# design.net
KiCad netlist of a schematic drawn in EasyEDA
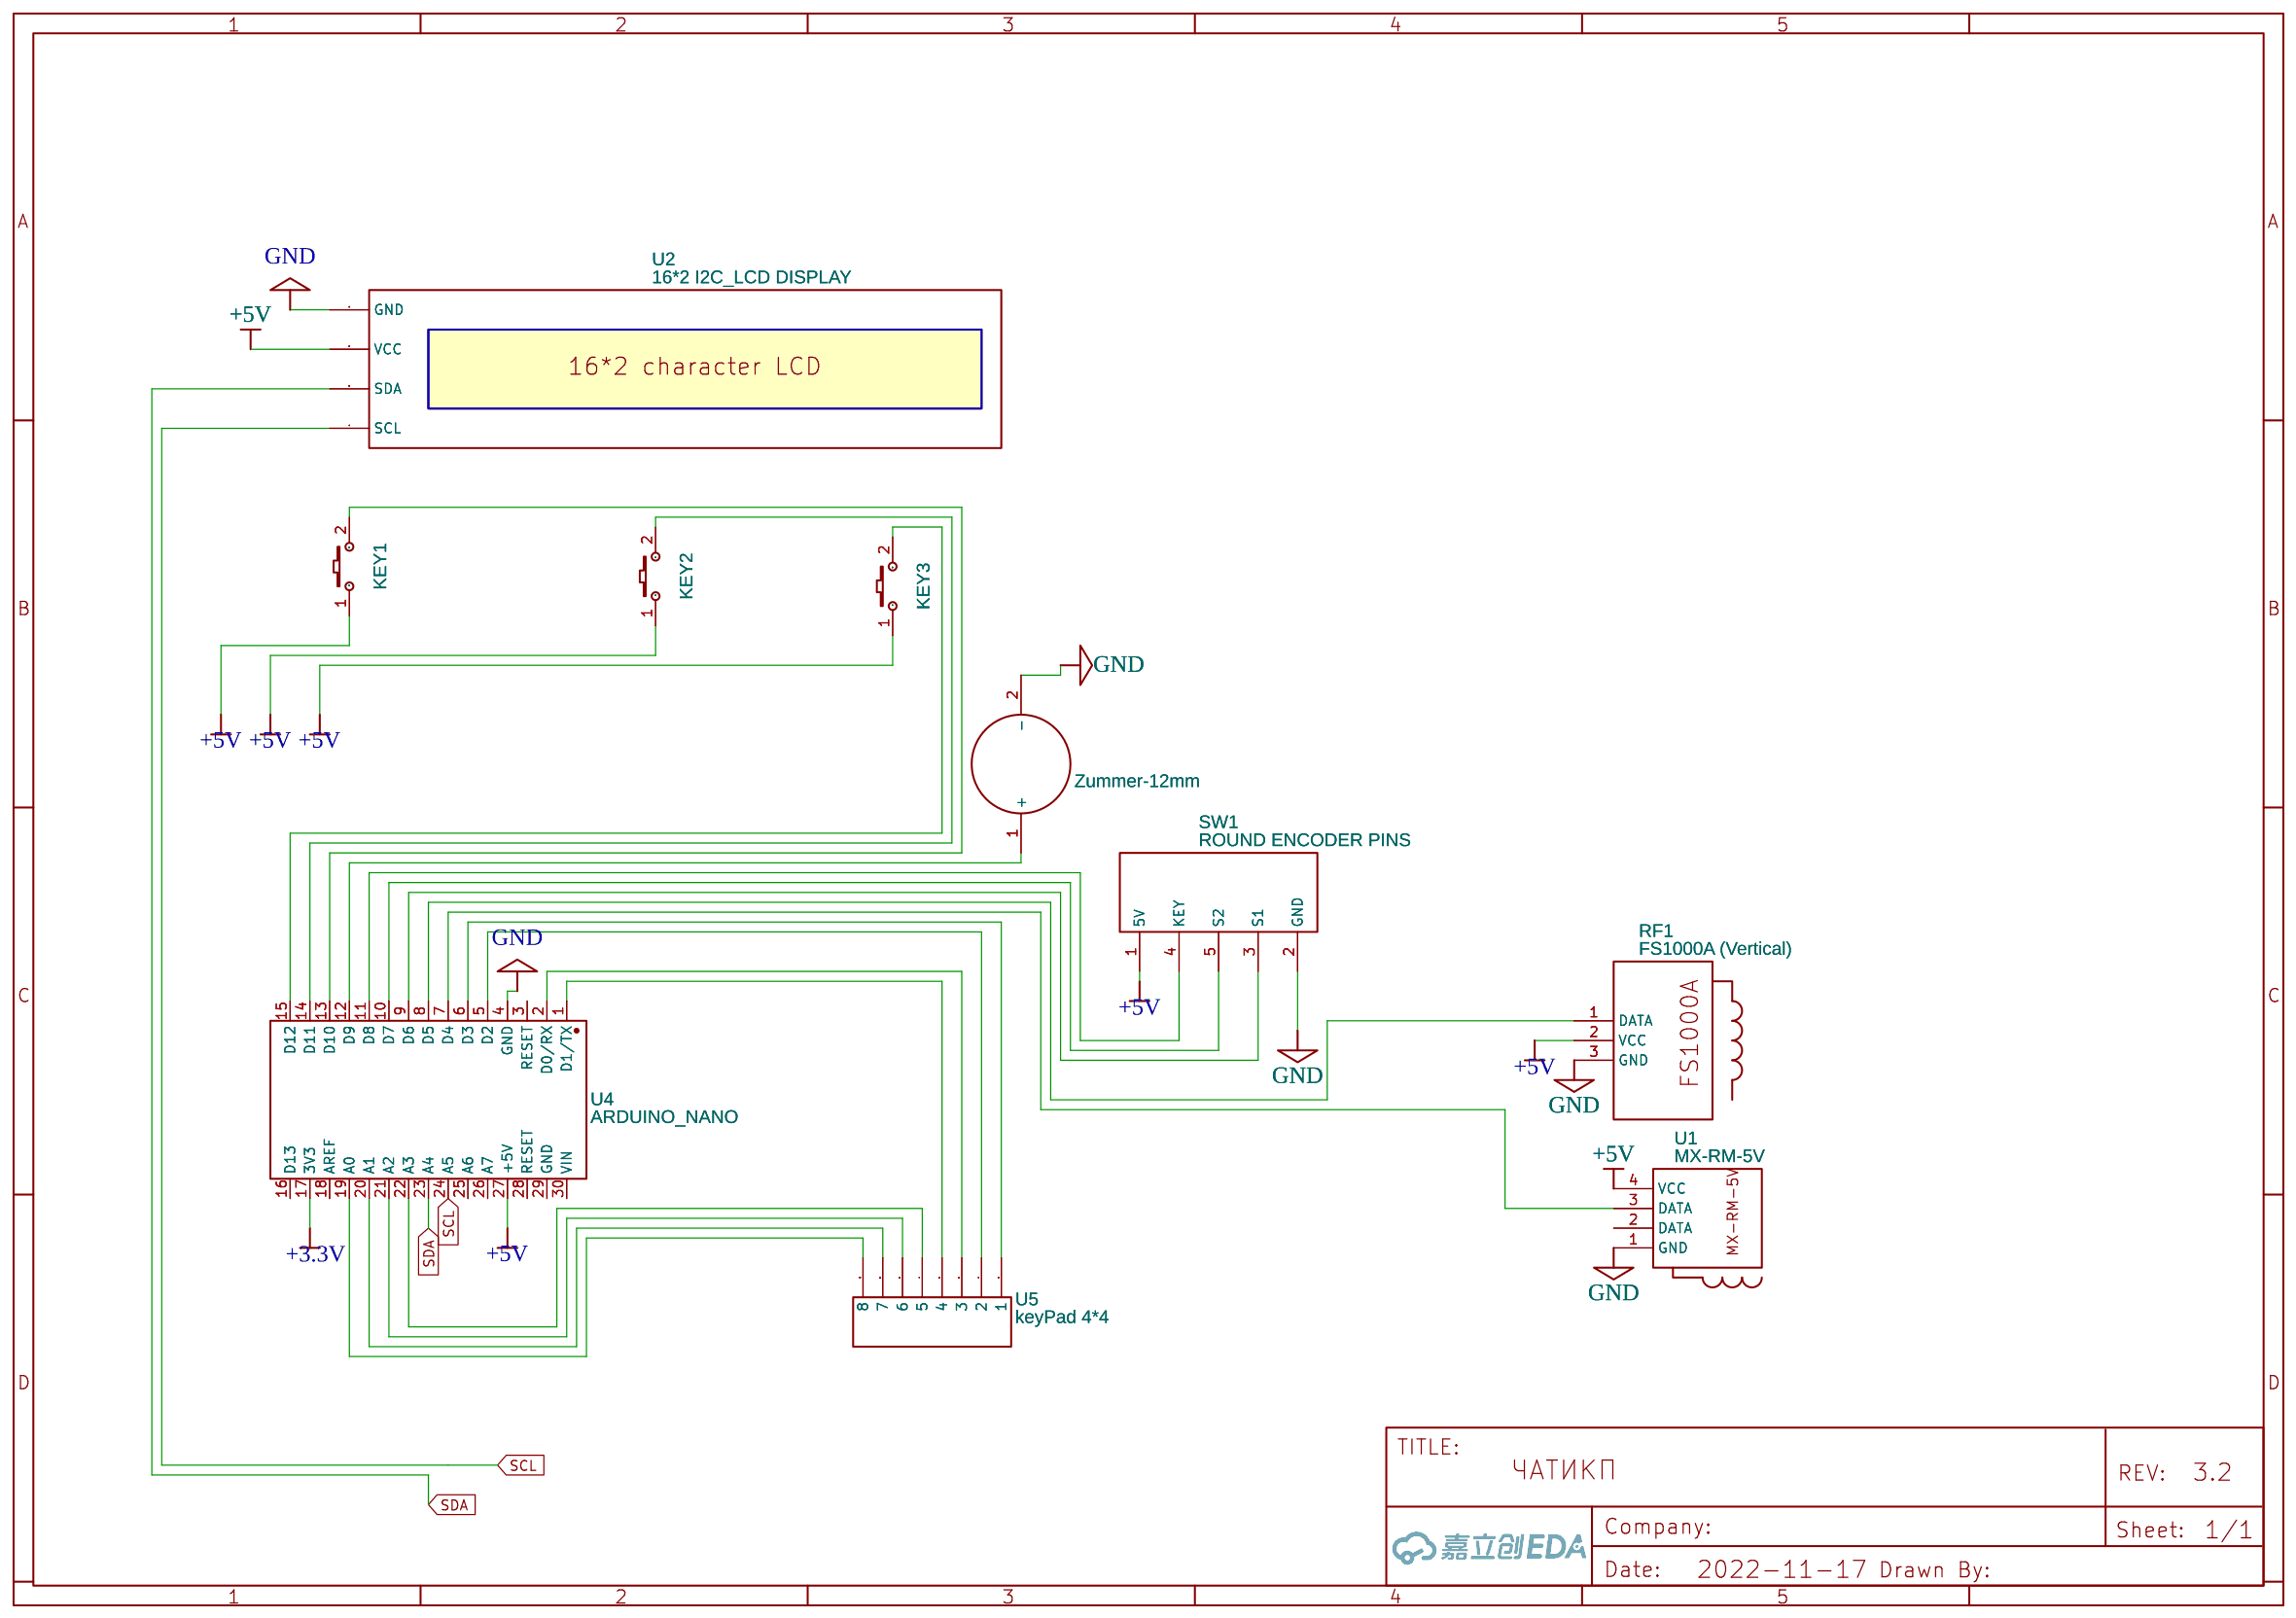
[diagram p0: schematic sheet]

(export (version "E")
  (design (tool "Eeschema 10.0.6"))
  (components
    (comp (ref "KEY1")
      (value "K2-3.6×6.1_SMD")
      (fields
        (field (name "BOM_Manufacturer Part") "K2-1107ST-A4SW-06")
        (field (name "BOM_Supplier Part") "C118141")
      )
      (libsource (lib "") (part "K2-3.6×6.1_SMD"))
    )
    (comp (ref "KEY2")
      (value "K2-3.6×6.1_SMD")
      (fields
        (field (name "BOM_Manufacturer Part") "K2-1107ST-A4SW-06")
        (field (name "BOM_Supplier Part") "C118141")
      )
      (libsource (lib "") (part "K2-3.6×6.1_SMD"))
    )
    (comp (ref "KEY3")
      (value "K2-3.6×6.1_SMD")
      (fields
        (field (name "BOM_Manufacturer Part") "K2-1107ST-A4SW-06")
        (field (name "BOM_Supplier Part") "C118141")
      )
      (libsource (lib "") (part "K2-3.6×6.1_SMD"))
    )
    (comp (ref "RF1") (value "FS1000A (Vertical)") (libsource (lib "") (part "FS1000A (Vertical)")))
    (comp (ref "SW1")
      (value "ROUND ENCODER PINS")
      (fields
        (field (name "BOM_Manufacturer Part") "PEC11R-4015F-S0024")
        (field (name "BOM_Supplier Part") "C143789")
      )
      (libsource (lib "") (part "ROUND ENCODER PINS"))
    )
    (comp (ref "U1") (value "MX-RM-5V") (libsource (lib "") (part "MX-RM-5V")))
    (comp (ref "U2")
      (value "16*2 I2C_LCD DISPLAY")
      (fields (field (name "BOM_Supplier Part") "undefined"))
      (libsource (lib "") (part "16*2 I2C_LCD DISPLAY"))
    )
    (comp (ref "U3") (value "Zummer-12mm") (libsource (lib "") (part "Y_Zummer-12mm")))
    (comp (ref "U4")
      (value "ARDUINO_NANO")
      (fields (field (name "BOM_Supplier Part") "C9900017879"))
      (libsource (lib "") (part "ARDUINO_NANO"))
    )
    (comp (ref "U5") (value "keyPad 4*4") (libsource (lib "") (part "keyPad 4*4")))
  )
  (nets
    (net (code "1") (name "+3.3V") (class "Default")
      (node (ref "U4") (pin "17") (pinfunction "3V3_17") (pintype "unspecified"))
    )
    (net (code "2") (name "+5V") (class "Default")
      (node (ref "KEY1") (pin "1") (pinfunction "1_1") (pintype "unspecified"))
      (node (ref "KEY2") (pin "1") (pinfunction "1_1") (pintype "unspecified"))
      (node (ref "KEY3") (pin "1") (pinfunction "1_1") (pintype "unspecified"))
      (node (ref "RF1") (pin "2") (pinfunction "VCC_2") (pintype "unspecified"))
      (node (ref "SW1") (pin "1") (pinfunction "5V_1") (pintype "unspecified"))
      (node (ref "U1") (pin "4") (pinfunction "VCC_4") (pintype "unspecified"))
      (node (ref "U2") (pin "2") (pinfunction "VCC_2") (pintype "unspecified"))
      (node (ref "U4") (pin "27") (pinfunction "+5V_27") (pintype "unspecified"))
    )
    (net (code "3") (name "GND") (class "Default")
      (node (ref "RF1") (pin "3") (pinfunction "GND_3") (pintype "unspecified"))
      (node (ref "SW1") (pin "2") (pinfunction "GND_2") (pintype "unspecified"))
      (node (ref "U1") (pin "1") (pinfunction "GND_1") (pintype "unspecified"))
      (node (ref "U2") (pin "1") (pinfunction "GND_1") (pintype "unspecified"))
      (node (ref "U3") (pin "2") (pinfunction "-_2") (pintype "unspecified"))
      (node (ref "U4") (pin "4") (pinfunction "GND_4") (pintype "unspecified"))
    )
    (net (code "4") (name "Net-(RF1-DATA)") (class "Default")
      (node (ref "RF1") (pin "1") (pinfunction "DATA_1") (pintype "unspecified"))
      (node (ref "U4") (pin "8") (pinfunction "D5_8") (pintype "unspecified"))
    )
    (net (code "5") (name "Net-(SW1-KEY)") (class "Default")
      (node (ref "SW1") (pin "4") (pinfunction "KEY_4") (pintype "unspecified"))
      (node (ref "U4") (pin "11") (pinfunction "D8_11") (pintype "unspecified"))
    )
    (net (code "6") (name "Net-(SW1-S1)") (class "Default")
      (node (ref "SW1") (pin "3") (pinfunction "S1_3") (pintype "unspecified"))
      (node (ref "U4") (pin "9") (pinfunction "D6_9") (pintype "unspecified"))
    )
    (net (code "7") (name "Net-(SW1-S2)") (class "Default")
      (node (ref "SW1") (pin "5") (pinfunction "S2_5") (pintype "unspecified"))
      (node (ref "U4") (pin "10") (pinfunction "D7_10") (pintype "unspecified"))
    )
    (net (code "8") (name "Net-(U3-+)") (class "Default")
      (node (ref "U3") (pin "1") (pinfunction "+_1") (pintype "unspecified"))
      (node (ref "U4") (pin "12") (pinfunction "D9_12") (pintype "unspecified"))
    )
    (net (code "9") (name "Net-(U4-A0)") (class "Default")
      (node (ref "U4") (pin "19") (pinfunction "A0_19") (pintype "unspecified"))
      (node (ref "U5") (pin "10") (pinfunction "8_10") (pintype "unspecified"))
    )
    (net (code "10") (name "Net-(U4-A1)") (class "Default")
      (node (ref "U4") (pin "20") (pinfunction "A1_20") (pintype "unspecified"))
      (node (ref "U5") (pin "9") (pinfunction "7_9") (pintype "unspecified"))
    )
    (net (code "11") (name "Net-(U4-A2)") (class "Default")
      (node (ref "U4") (pin "21") (pinfunction "A2_21") (pintype "unspecified"))
      (node (ref "U5") (pin "8") (pinfunction "6_8") (pintype "unspecified"))
    )
    (net (code "12") (name "Net-(U4-A3)") (class "Default")
      (node (ref "U4") (pin "22") (pinfunction "A3_22") (pintype "unspecified"))
      (node (ref "U5") (pin "7") (pinfunction "5_7") (pintype "unspecified"))
    )
    (net (code "13") (name "Net-(U4-D0{slash}RX)") (class "Default")
      (node (ref "U4") (pin "2") (pinfunction "D0/RX_2") (pintype "unspecified"))
      (node (ref "U5") (pin "5") (pinfunction "3_5") (pintype "unspecified"))
    )
    (net (code "14") (name "Net-(U4-D1{slash}TX)") (class "Default")
      (node (ref "U4") (pin "1") (pinfunction "D1/TX_1") (pintype "unspecified"))
      (node (ref "U5") (pin "6") (pinfunction "4_6") (pintype "unspecified"))
    )
    (net (code "15") (name "Net-(U4-D2)") (class "Default")
      (node (ref "U4") (pin "5") (pinfunction "D2_5") (pintype "unspecified"))
      (node (ref "U5") (pin "4") (pinfunction "2_4") (pintype "unspecified"))
    )
    (net (code "16") (name "Net-(U4-D3)") (class "Default")
      (node (ref "U4") (pin "6") (pinfunction "D3_6") (pintype "unspecified"))
      (node (ref "U5") (pin "3") (pinfunction "1_3") (pintype "unspecified"))
    )
    (net (code "17") (name "Net-(U4-D4)") (class "Default")
      (node (ref "U1") (pin "3") (pinfunction "DATA_3") (pintype "unspecified"))
      (node (ref "U4") (pin "7") (pinfunction "D4_7") (pintype "unspecified"))
    )
    (net (code "18") (name "Net-(U4-D10)") (class "Default")
      (node (ref "KEY1") (pin "2") (pinfunction "2_2") (pintype "unspecified"))
      (node (ref "U4") (pin "13") (pinfunction "D10_13") (pintype "unspecified"))
    )
    (net (code "19") (name "Net-(U4-D11)") (class "Default")
      (node (ref "KEY2") (pin "2") (pinfunction "2_2") (pintype "unspecified"))
      (node (ref "U4") (pin "14") (pinfunction "D11_14") (pintype "unspecified"))
    )
    (net (code "20") (name "Net-(U4-D12)") (class "Default")
      (node (ref "KEY3") (pin "2") (pinfunction "2_2") (pintype "unspecified"))
      (node (ref "U4") (pin "15") (pinfunction "D12_15") (pintype "unspecified"))
    )
    (net (code "21") (name "SCL") (class "Default")
      (node (ref "U2") (pin "4") (pinfunction "SCL_4") (pintype "unspecified"))
      (node (ref "U4") (pin "24") (pinfunction "A5_24") (pintype "unspecified"))
    )
    (net (code "22") (name "SDA") (class "Default")
      (node (ref "U2") (pin "3") (pinfunction "SDA_3") (pintype "unspecified"))
      (node (ref "U4") (pin "23") (pinfunction "A4_23") (pintype "unspecified"))
    )
    (net (code "23") (name "unconnected-(U1-DATA-Pad2)") (class "Default")
      (node (ref "U1") (pin "2") (pinfunction "DATA_2") (pintype "unspecified"))
    )
    (net (code "24") (name "unconnected-(U4-A6-Pad25)") (class "Default")
      (node (ref "U4") (pin "25") (pinfunction "A6_25") (pintype "unspecified"))
    )
    (net (code "25") (name "unconnected-(U4-A7-Pad26)") (class "Default")
      (node (ref "U4") (pin "26") (pinfunction "A7_26") (pintype "unspecified"))
    )
    (net (code "26") (name "unconnected-(U4-AREF-Pad18)") (class "Default")
      (node (ref "U4") (pin "18") (pinfunction "AREF_18") (pintype "unspecified"))
    )
    (net (code "27") (name "unconnected-(U4-D13-Pad16)") (class "Default")
      (node (ref "U4") (pin "16") (pinfunction "D13_16") (pintype "unspecified"))
    )
    (net (code "28") (name "unconnected-(U4-GND-Pad29)") (class "Default")
      (node (ref "U4") (pin "29") (pinfunction "GND_29") (pintype "unspecified"))
    )
    (net (code "29") (name "unconnected-(U4-RESET-Pad3)") (class "Default")
      (node (ref "U4") (pin "3") (pinfunction "RESET_3") (pintype "unspecified"))
    )
    (net (code "30") (name "unconnected-(U4-RESET-Pad28)") (class "Default")
      (node (ref "U4") (pin "28") (pinfunction "RESET_28") (pintype "unspecified"))
    )
    (net (code "31") (name "unconnected-(U4-VIN-Pad30)") (class "Default")
      (node (ref "U4") (pin "30") (pinfunction "VIN_30") (pintype "unspecified"))
    )
  )
)
